# fireAlarm.net
KiCad netlist of a schematic drawn in Altium Designer
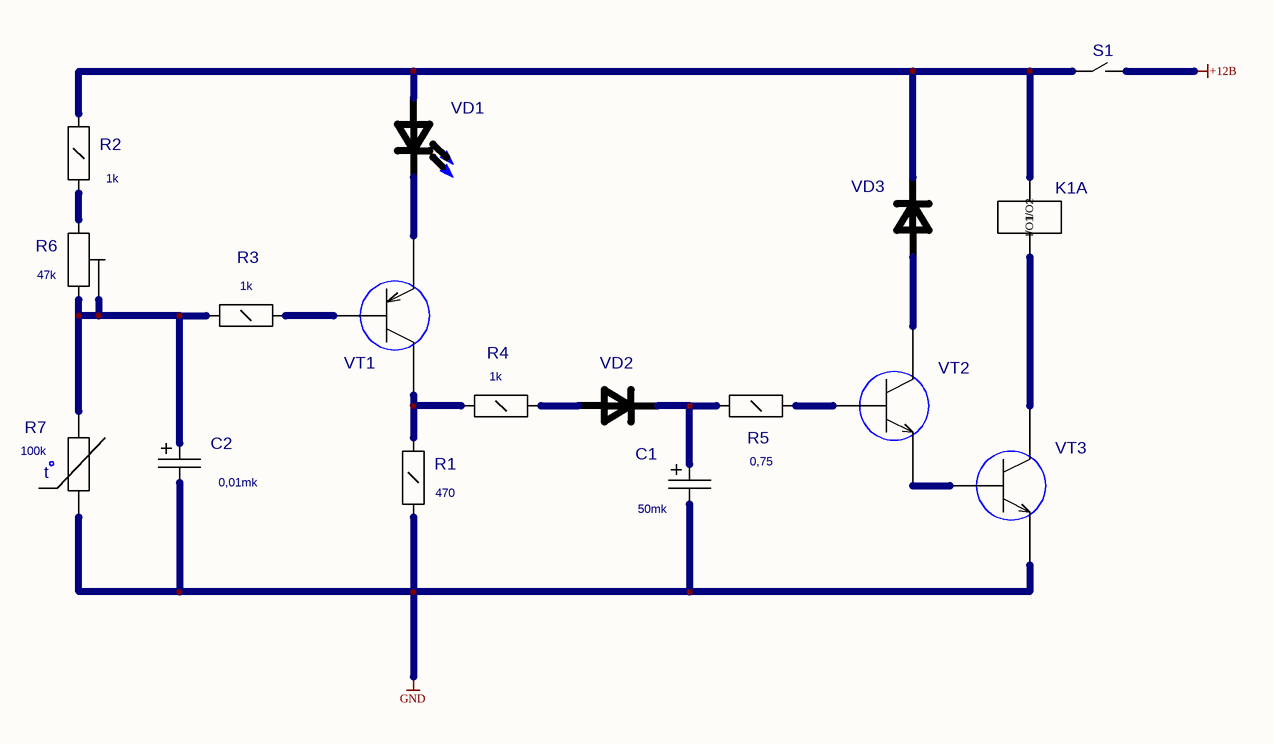
[diagram p0: fireAlarm.SchDoc]

(export (version "E")
  (design (tool "Eeschema 10.0.6"))
  (components
    (comp (ref "C1")
      (value "50mk")
      (footprint "CE6032_C")
      (description "CE6032-C")
      (libsource (lib "*") (part "CE6032-C"))
    )
    (comp (ref "C2")
      (value "0,01mk")
      (footprint "CE6032_C")
      (description "CE6032-C")
      (libsource (lib "*") (part "CE6032-C"))
    )
    (comp (ref "K1") (value "РЭС-64") (footprint "RES64") (libsource (lib "*") (part "РЭС-64")))
    (comp (ref "R1")
      (value "470")
      (footprint "C2-33H-0.25W")
      (description "C2-33H-0.25W_OLD_UGO")
      (fields (field (name "AUTOR") "pcbdesigner.ru"))
      (libsource (lib "*") (part "C2-33H-0.25W_OLD_UGO"))
    )
    (comp (ref "R2")
      (value "1k")
      (footprint "C2-33H-0.25W")
      (description "C2-33H-0.25W_OLD_UGO")
      (fields (field (name "AUTOR") "pcbdesigner.ru"))
      (libsource (lib "*") (part "C2-33H-0.25W_OLD_UGO"))
    )
    (comp (ref "R3")
      (value "1k")
      (footprint "C2-33H-0.25W")
      (description "C2-33H-0.25W_OLD_UGO")
      (fields (field (name "AUTOR") "pcbdesigner.ru"))
      (libsource (lib "*") (part "C2-33H-0.25W_OLD_UGO"))
    )
    (comp (ref "R4")
      (value "1k")
      (footprint "C2-33H-0.25W")
      (description "C2-33H-0.25W_OLD_UGO")
      (fields (field (name "AUTOR") "pcbdesigner.ru"))
      (libsource (lib "*") (part "C2-33H-0.25W_OLD_UGO"))
    )
    (comp (ref "R5")
      (value "0,75")
      (footprint "C2-33H-0.25W")
      (description "C2-33H-0.25W_OLD_UGO")
      (fields (field (name "AUTOR") "pcbdesigner.ru"))
      (libsource (lib "*") (part "C2-33H-0.25W_OLD_UGO"))
    )
    (comp (ref "R6")
      (value "47k")
      (footprint "3006P")
      (description "3006W")
      (libsource (lib "*") (part "3006W"))
    )
    (comp (ref "R7")
      (value "100k")
      (footprint "PTC-3")
      (description "PTC-3")
      (fields (field (name "AUTHOR") "pcbdesigner.ru"))
      (libsource (lib "*") (part "PTC-3"))
    )
    (comp (ref "S1")
      (value "8AS9M2RE")
      (footprint "8AS9M2RE")
      (fields (field (name "AUTHOR") "pcbdesigner.ru"))
      (libsource (lib "*") (part "8AS9M2RE"))
    )
    (comp (ref "VD1") (value "АЛ307КМ") (footprint "LED-5MM") (libsource (lib "*") (part "АЛ307КМ")))
    (comp (ref "VD2") (value "КД522А") (footprint "КД521(522)") (libsource (lib "*") (part "КД522А")))
    (comp (ref "VD3") (value "КД503А") (footprint "КД503А") (libsource (lib "*") (part "КД503А")))
    (comp (ref "VT1") (value "КТ3107Е") (footprint "TO-92-4") (libsource (lib "*") (part "КТ3107Е")))
    (comp (ref "VT2") (value "КТ312") (footprint "КТ312") (libsource (lib "*") (part "КТ312")))
    (comp (ref "VT3") (value "КТ608Б") (footprint "КТ605") (libsource (lib "*") (part "КТ608Б")))
  )
  (nets
    (net (code "1") (name "+12B") (class "Default")
      (node (ref "S1") (pin "1") (pinfunction "1_1") (pintype "passive"))
    )
    (net (code "2") (name "GND") (class "Default")
      (node (ref "C1") (pin "2") (pinfunction "2_2") (pintype "passive"))
      (node (ref "C2") (pin "2") (pinfunction "2_2") (pintype "passive"))
      (node (ref "R1") (pin "1") (pinfunction "1_1") (pintype "passive"))
      (node (ref "R7") (pin "1") (pinfunction "1_1") (pintype "passive"))
      (node (ref "VT3") (pin "2") (pinfunction "E_2") (pintype "passive"))
    )
    (net (code "3") (name "Net-(C2-Pad1)") (class "Default")
      (node (ref "C2") (pin "1") (pinfunction "1_1") (pintype "passive"))
      (node (ref "R3") (pin "2") (pinfunction "2_2") (pintype "passive"))
      (node (ref "R6") (pin "2") (pinfunction "2_2") (pintype "passive"))
      (node (ref "R6") (pin "3") (pinfunction "3_3") (pintype "passive"))
      (node (ref "R7") (pin "2") (pinfunction "2_2") (pintype "passive"))
    )
    (net (code "4") (name "Net-(K1-I{slash}O1)") (class "Default")
      (node (ref "K1") (pin "1") (pinfunction "I/O1_1") (pintype "passive"))
      (node (ref "VT3") (pin "3") (pinfunction "K_3") (pintype "passive"))
    )
    (net (code "5") (name "Net-(K1-I{slash}O2)") (class "Default")
      (node (ref "K1") (pin "2") (pinfunction "I/O2_2") (pintype "passive"))
      (node (ref "R2") (pin "2") (pinfunction "2_2") (pintype "passive"))
      (node (ref "S1") (pin "2") (pinfunction "2_2") (pintype "passive"))
      (node (ref "VD1") (pin "1") (pinfunction "A_1") (pintype "passive"))
      (node (ref "VD3") (pin "K") (pinfunction "K_K") (pintype "passive"))
    )
    (net (code "6") (name "Net-(R1-Pad2)") (class "Default")
      (node (ref "R1") (pin "2") (pinfunction "2_2") (pintype "passive"))
      (node (ref "R4") (pin "2") (pinfunction "2_2") (pintype "passive"))
      (node (ref "VT1") (pin "E") (pinfunction "E_E") (pintype "passive"))
    )
    (net (code "7") (name "Net-(R2-Pad1)") (class "Default")
      (node (ref "R2") (pin "1") (pinfunction "1_1") (pintype "passive"))
      (node (ref "R6") (pin "1") (pinfunction "1_1") (pintype "passive"))
    )
    (net (code "8") (name "Net-(R3-Pad1)") (class "Default")
      (node (ref "R3") (pin "1") (pinfunction "1_1") (pintype "passive"))
      (node (ref "VT1") (pin "B") (pinfunction "B_B") (pintype "passive"))
    )
    (net (code "9") (name "Net-(R5-Pad1)") (class "Default")
      (node (ref "R5") (pin "1") (pinfunction "1_1") (pintype "passive"))
      (node (ref "VT2") (pin "B") (pinfunction "B_B") (pintype "passive"))
    )
    (net (code "10") (name "Net-(VD1-K)") (class "Default")
      (node (ref "VD1") (pin "2") (pinfunction "K_2") (pintype "passive"))
      (node (ref "VT1") (pin "C") (pinfunction "C_C") (pintype "passive"))
    )
    (net (code "11") (name "Net-(VD2-A)") (class "Default")
      (node (ref "R4") (pin "1") (pinfunction "1_1") (pintype "passive"))
      (node (ref "VD2") (pin "1") (pinfunction "A_1") (pintype "passive"))
    )
    (net (code "12") (name "Net-(VD2-K)") (class "Default")
      (node (ref "C1") (pin "1") (pinfunction "1_1") (pintype "passive"))
      (node (ref "R5") (pin "2") (pinfunction "2_2") (pintype "passive"))
      (node (ref "VD2") (pin "2") (pinfunction "K_2") (pintype "passive"))
    )
    (net (code "13") (name "Net-(VD3-PadA)") (class "Default")
      (node (ref "VD3") (pin "A") (pinfunction "A_A") (pintype "passive"))
      (node (ref "VT2") (pin "K") (pinfunction "K_K") (pintype "passive"))
    )
    (net (code "14") (name "Net-(VT3-B)") (class "Default")
      (node (ref "VT2") (pin "E") (pinfunction "E_E") (pintype "passive"))
      (node (ref "VT3") (pin "1") (pinfunction "B_1") (pintype "passive"))
    )
    (net (code "15") (name "unconnected-(K1-Pad5)") (class "Default")
      (node (ref "K1") (pin "5") (pintype "passive"))
    )
  )
)
